# DAC_Channel_12.net
KiCad netlist of a schematic drawn in Altium Designer
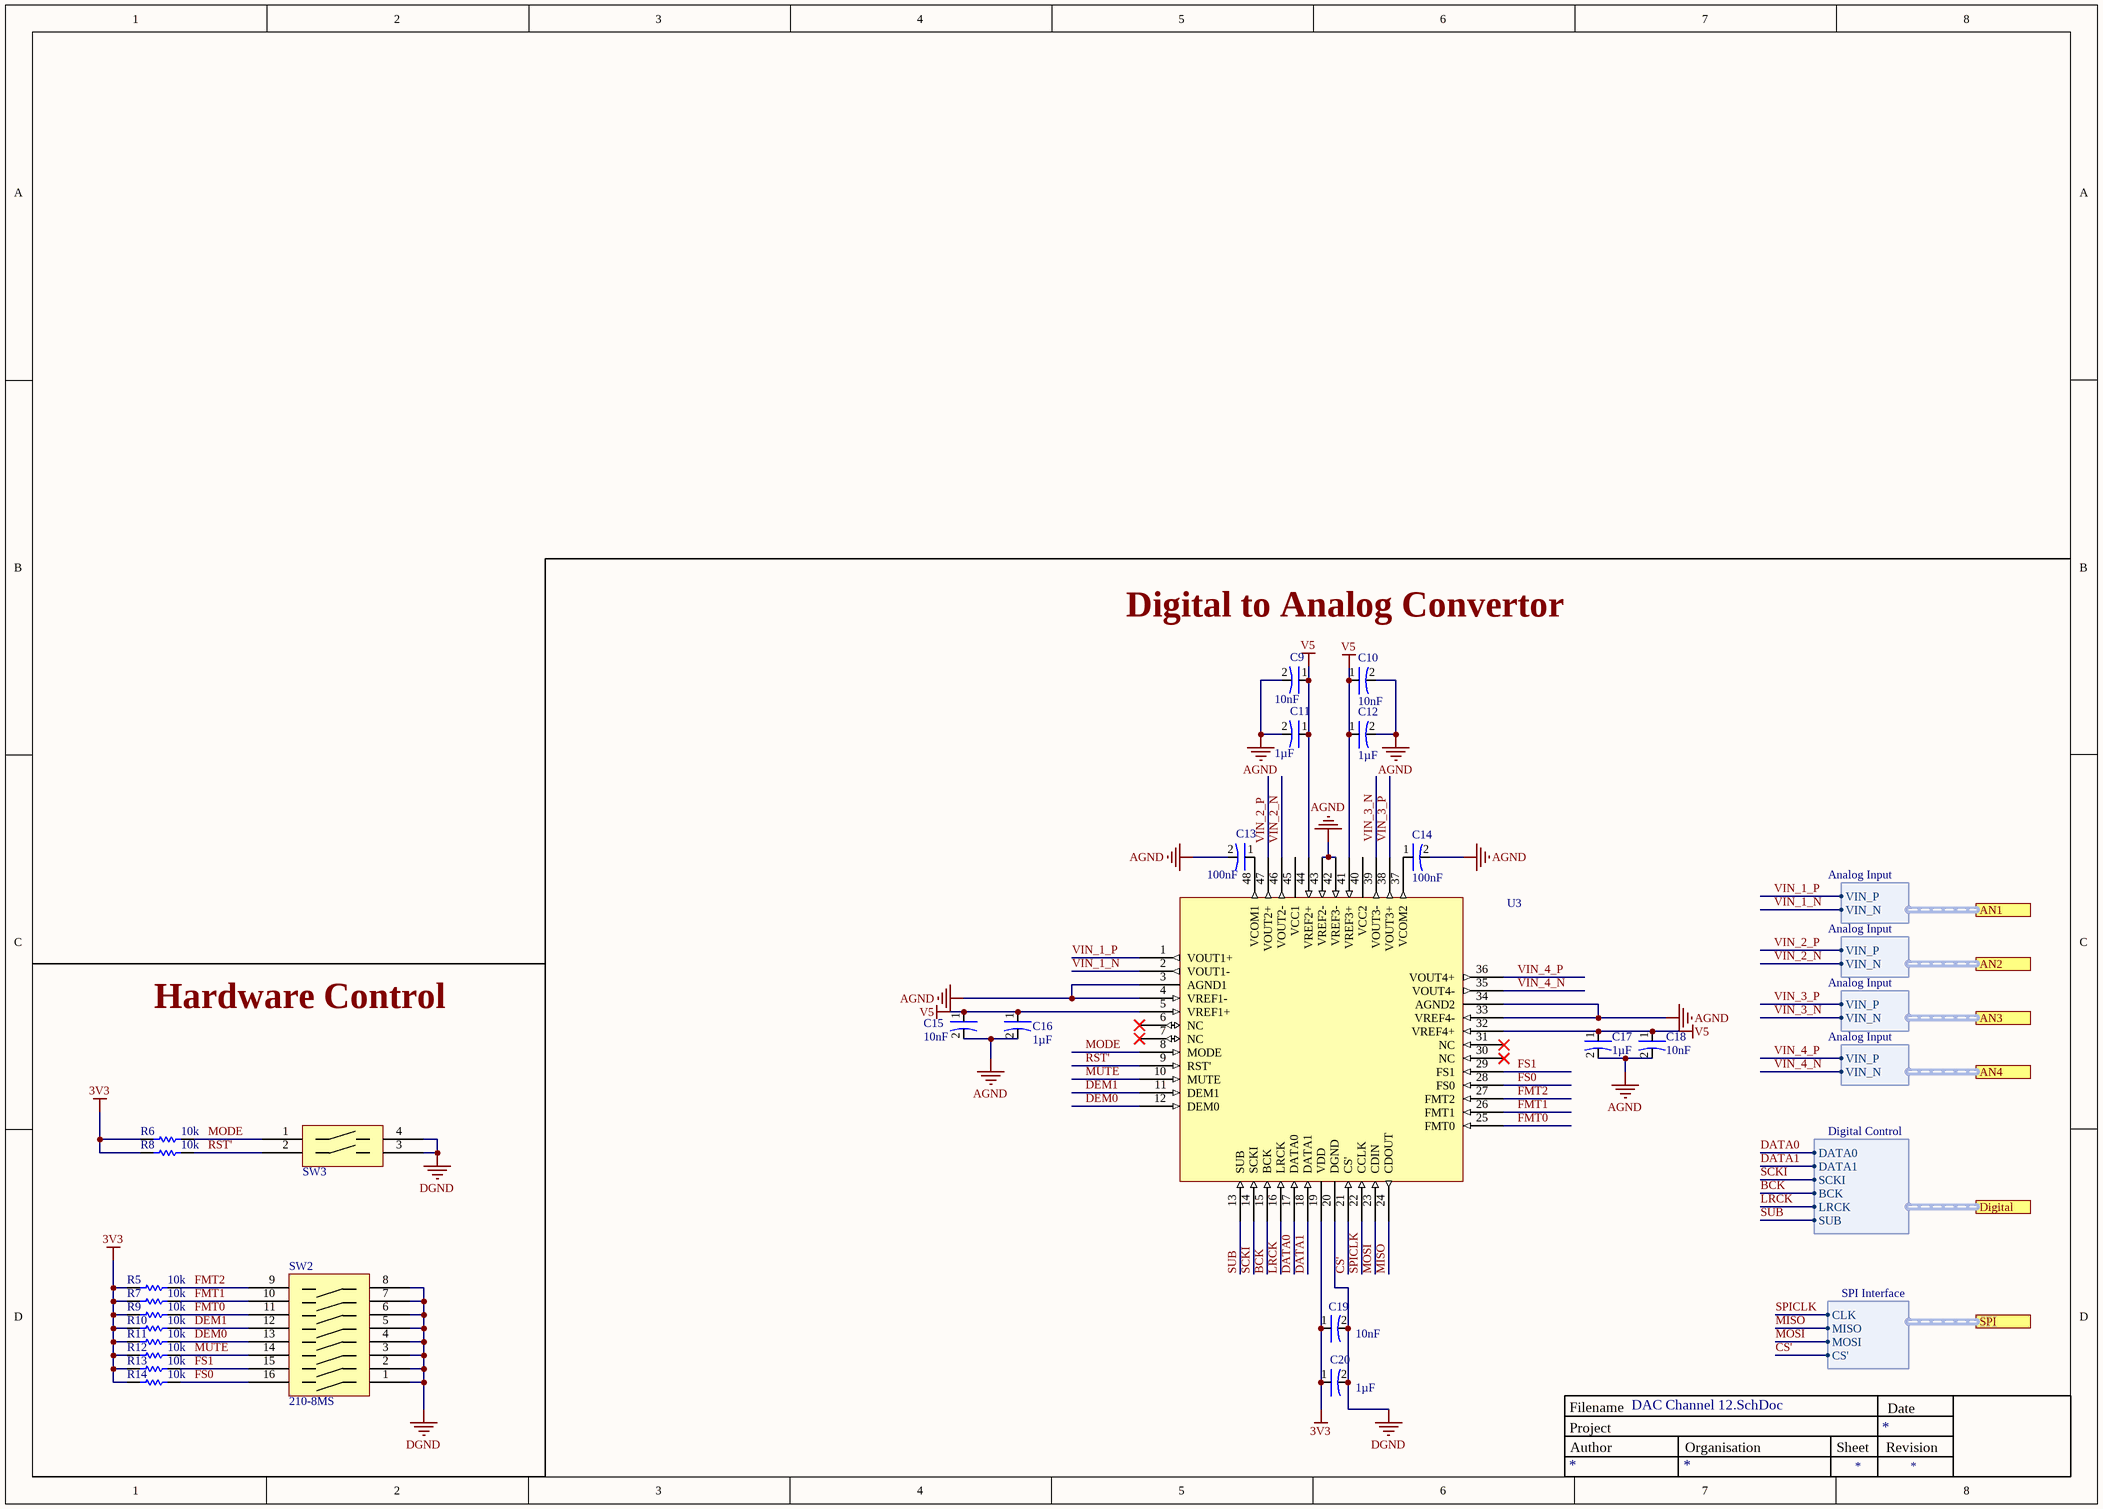
[diagram p0: DAC Channel 12.SchDoc]

(export (version "E")
  (design (tool "Eeschema 10.0.6"))
  (components
    (comp (ref "C9")
      (value "10nF")
      (footprint "0805-M")
      (description "CAP-10nF-CER-0805-50V-X7R-10%")
      (fields
        (field (name "MANUFACTURER") "Generic")
        (field (name "Comment") "CAP 10nF CER 0805 50V X7R 10%")
      )
      (libsource (lib "") (part "Symbol_1"))
    )
    (comp (ref "C10")
      (value "10nF")
      (footprint "0805-M")
      (description "CAP-10nF-CER-0805-50V-X7R-10%")
      (fields
        (field (name "MANUFACTURER") "Generic")
        (field (name "Comment") "CAP 10nF CER 0805 50V X7R 10%")
      )
      (libsource (lib "") (part "Symbol_2"))
    )
    (comp (ref "C11")
      (value "1µF")
      (footprint "0805-L")
      (description "CAP-1uF-CER-0805-50V-X7R-10%")
      (fields (field (name "MANUFACTURER") "Generic") (field (name "Comment") "CAP 1uF CER 0805 50V X7R 10%"))
      (libsource (lib "") (part "Symbol_1"))
    )
    (comp (ref "C12")
      (value "1µF")
      (footprint "0805-L")
      (description "CAP-1uF-CER-0805-50V-X7R-10%")
      (fields (field (name "MANUFACTURER") "Generic") (field (name "Comment") "CAP 1uF CER 0805 50V X7R 10%"))
      (libsource (lib "") (part "Symbol_2"))
    )
    (comp (ref "C13")
      (value "100nF")
      (footprint "0603-M")
      (description "CAP-100nF-CER-0603-50V-X7R-5%")
      (fields
        (field (name "MANUFACTURER") "Generic")
        (field (name "Comment") "CAP 100nF CER 0603 50V X7R 5%")
      )
      (libsource (lib "") (part "Symbol_1"))
    )
    (comp (ref "C14")
      (value "100nF")
      (footprint "0603-M")
      (description "CAP-100nF-CER-0603-50V-X7R-5%")
      (fields
        (field (name "MANUFACTURER") "Generic")
        (field (name "Comment") "CAP 100nF CER 0603 50V X7R 5%")
      )
      (libsource (lib "") (part "Symbol_2"))
    )
    (comp (ref "C15")
      (value "10nF")
      (footprint "0805-M")
      (description "CAP-10nF-CER-0805-50V-X7R-10%")
      (fields
        (field (name "MANUFACTURER") "Generic")
        (field (name "Comment") "CAP 10nF CER 0805 50V X7R 10%")
      )
      (libsource (lib "") (part "Symbol_3"))
    )
    (comp (ref "C16")
      (value "1µF")
      (footprint "0805-L")
      (description "CAP-1uF-CER-0805-50V-X7R-10%")
      (fields (field (name "MANUFACTURER") "Generic") (field (name "Comment") "CAP 1uF CER 0805 50V X7R 10%"))
      (libsource (lib "") (part "Symbol_3"))
    )
    (comp (ref "C17")
      (value "1µF")
      (footprint "0805-L")
      (description "CAP-1uF-CER-0805-50V-X7R-10%")
      (fields (field (name "MANUFACTURER") "Generic") (field (name "Comment") "CAP 1uF CER 0805 50V X7R 10%"))
      (libsource (lib "") (part "Symbol_3"))
    )
    (comp (ref "C18")
      (value "10nF")
      (footprint "0805-M")
      (description "CAP-10nF-CER-0805-50V-X7R-10%")
      (fields
        (field (name "MANUFACTURER") "Generic")
        (field (name "Comment") "CAP 10nF CER 0805 50V X7R 10%")
      )
      (libsource (lib "") (part "Symbol_3"))
    )
    (comp (ref "C19")
      (value "10nF")
      (footprint "0805-M")
      (description "CAP-10nF-CER-0805-50V-X7R-10%")
      (fields
        (field (name "MANUFACTURER") "Generic")
        (field (name "Comment") "CAP 10nF CER 0805 50V X7R 10%")
      )
      (libsource (lib "") (part "Symbol_1"))
    )
    (comp (ref "C20")
      (value "1µF")
      (footprint "0805-L")
      (description "CAP-1uF-CER-0805-50V-X7R-10%")
      (fields (field (name "MANUFACTURER") "Generic") (field (name "Comment") "CAP 1uF CER 0805 50V X7R 10%"))
      (libsource (lib "") (part "Symbol_1"))
    )
    (comp (ref "R5")
      (value "10k")
      (footprint "0805-M")
      (description "RES-10k-0805-125mW-1%")
      (fields (field (name "MANUFACTURER") "Generic") (field (name "Comment") "RES 10k 0805 125mW 1%"))
      (libsource (lib "University of Malta - MEMENTO") (part "Symbol"))
    )
    (comp (ref "R6")
      (value "10k")
      (footprint "0805-M")
      (description "RES-10k-0805-125mW-1%")
      (fields (field (name "MANUFACTURER") "Generic") (field (name "Comment") "RES 10k 0805 125mW 1%"))
      (libsource (lib "University of Malta - MEMENTO") (part "Symbol"))
    )
    (comp (ref "R7")
      (value "10k")
      (footprint "0805-M")
      (description "RES-10k-0805-125mW-1%")
      (fields (field (name "MANUFACTURER") "Generic") (field (name "Comment") "RES 10k 0805 125mW 1%"))
      (libsource (lib "University of Malta - MEMENTO") (part "Symbol"))
    )
    (comp (ref "R8")
      (value "10k")
      (footprint "0805-M")
      (description "RES-10k-0805-125mW-1%")
      (fields (field (name "MANUFACTURER") "Generic") (field (name "Comment") "RES 10k 0805 125mW 1%"))
      (libsource (lib "University of Malta - MEMENTO") (part "Symbol"))
    )
    (comp (ref "R9")
      (value "10k")
      (footprint "0805-M")
      (description "RES-10k-0805-125mW-1%")
      (fields (field (name "MANUFACTURER") "Generic") (field (name "Comment") "RES 10k 0805 125mW 1%"))
      (libsource (lib "University of Malta - MEMENTO") (part "Symbol"))
    )
    (comp (ref "R10")
      (value "10k")
      (footprint "0805-M")
      (description "RES-10k-0805-125mW-1%")
      (fields (field (name "MANUFACTURER") "Generic") (field (name "Comment") "RES 10k 0805 125mW 1%"))
      (libsource (lib "University of Malta - MEMENTO") (part "Symbol"))
    )
    (comp (ref "R11")
      (value "10k")
      (footprint "0805-M")
      (description "RES-10k-0805-125mW-1%")
      (fields (field (name "MANUFACTURER") "Generic") (field (name "Comment") "RES 10k 0805 125mW 1%"))
      (libsource (lib "University of Malta - MEMENTO") (part "Symbol"))
    )
    (comp (ref "R12")
      (value "10k")
      (footprint "0805-M")
      (description "RES-10k-0805-125mW-1%")
      (fields (field (name "MANUFACTURER") "Generic") (field (name "Comment") "RES 10k 0805 125mW 1%"))
      (libsource (lib "University of Malta - MEMENTO") (part "Symbol"))
    )
    (comp (ref "R13")
      (value "10k")
      (footprint "0805-M")
      (description "RES-10k-0805-125mW-1%")
      (fields (field (name "MANUFACTURER") "Generic") (field (name "Comment") "RES 10k 0805 125mW 1%"))
      (libsource (lib "University of Malta - MEMENTO") (part "Symbol"))
    )
    (comp (ref "R14")
      (value "10k")
      (footprint "0805-M")
      (description "RES-10k-0805-125mW-1%")
      (fields (field (name "MANUFACTURER") "Generic") (field (name "Comment") "RES 10k 0805 125mW 1%"))
      (libsource (lib "University of Malta - MEMENTO") (part "Symbol"))
    )
    (comp (ref "SW2")
      (value "210-8MS")
      (footprint "210-8MS")
      (description "SWITCH DIP SMD SPST 8 100mA 50V")
      (fields (field (name "MANUFACTURER") "C&K Components") (field (name "DESIGN ITEM ID") "210-8MS"))
      (libsource (lib "University of Malta - MEMENTO") (part "210-8MS"))
    )
    (comp (ref "SW3")
      (value "210-2MS")
      (footprint "210-2MS-Footprint-1")
      (description "SWITCH DIP SPST 2 100mA 50V")
      (libsource (lib "University of Malta - MEMENTO") (part "210-2MS"))
    )
    (comp (ref "U3")
      (value "PCM4104PFBR")
      (footprint "CQFP50P1170X1170X100-48N")
      (description "Converters - Digital to Analog (DAC) High-End 24-Bit 192kHz, 4-Ch D-S DAC")
      (libsource (lib "University of Malta - MEMENTO") (part "PCM4104PFBR"))
    )
  )
  (nets
    (net (code "7") (name "/BCK") (class "Default")
      (node (ref "U3") (pin "15") (pinfunction "BCK_15") (pintype "input"))
    )
    (net (code "8") (name "/CS'") (class "Default")
      (node (ref "U3") (pin "21") (pinfunction "CS'_21") (pintype "input"))
    )
    (net (code "9") (name "/DATA0") (class "Default")
      (node (ref "U3") (pin "17") (pinfunction "DATA0_17") (pintype "input"))
    )
    (net (code "10") (name "/DATA1") (class "Default")
      (node (ref "U3") (pin "18") (pinfunction "DATA1_18") (pintype "input"))
    )
    (net (code "11") (name "/DEM0") (class "Default")
      (node (ref "R11") (pin "1") (pinfunction "1_1") (pintype "passive"))
      (node (ref "SW2") (pin "13") (pinfunction "SW4.in_13") (pintype "passive"))
      (node (ref "U3") (pin "12") (pinfunction "DEM0_12") (pintype "input"))
    )
    (net (code "12") (name "/DEM1") (class "Default")
      (node (ref "R10") (pin "1") (pinfunction "1_1") (pintype "passive"))
      (node (ref "SW2") (pin "12") (pinfunction "SW1.in_12") (pintype "passive"))
      (node (ref "U3") (pin "11") (pinfunction "DEM1_11") (pintype "input"))
    )
    (net (code "13") (name "/FMT0") (class "Default")
      (node (ref "R9") (pin "1") (pinfunction "1_1") (pintype "passive"))
      (node (ref "SW2") (pin "11") (pinfunction "SW2.in_11") (pintype "passive"))
      (node (ref "U3") (pin "25") (pinfunction "FMT0_25") (pintype "input"))
    )
    (net (code "14") (name "/FMT1") (class "Default")
      (node (ref "R7") (pin "1") (pinfunction "1_1") (pintype "passive"))
      (node (ref "SW2") (pin "10") (pinfunction "SW3.in_10") (pintype "passive"))
      (node (ref "U3") (pin "26") (pinfunction "FMT1_26") (pintype "input"))
    )
    (net (code "15") (name "/FMT2") (class "Default")
      (node (ref "R5") (pin "1") (pinfunction "1_1") (pintype "passive"))
      (node (ref "SW2") (pin "9") (pinfunction "SW4.in_9") (pintype "passive"))
      (node (ref "U3") (pin "27") (pinfunction "FMT2_27") (pintype "input"))
    )
    (net (code "16") (name "/FS0") (class "Default")
      (node (ref "R14") (pin "1") (pinfunction "1_1") (pintype "passive"))
      (node (ref "SW2") (pin "16") (pinfunction "SW1_16") (pintype "passive"))
      (node (ref "U3") (pin "28") (pinfunction "FS0_28") (pintype "input"))
    )
    (net (code "17") (name "/FS1") (class "Default")
      (node (ref "R13") (pin "1") (pinfunction "1_1") (pintype "passive"))
      (node (ref "SW2") (pin "15") (pinfunction "SW2.in_15") (pintype "passive"))
      (node (ref "U3") (pin "29") (pinfunction "FS1_29") (pintype "input"))
    )
    (net (code "18") (name "/LRCK") (class "Default")
      (node (ref "U3") (pin "16") (pinfunction "LRCK_16") (pintype "input"))
    )
    (net (code "19") (name "/MISO") (class "Default")
      (node (ref "U3") (pin "24") (pinfunction "CDOUT_24") (pintype "output"))
    )
    (net (code "20") (name "/MODE") (class "Default")
      (node (ref "R6") (pin "1") (pinfunction "1_1") (pintype "passive"))
      (node (ref "SW3") (pin "1") (pinfunction "1_1") (pintype "passive"))
      (node (ref "U3") (pin "8") (pinfunction "MODE_8") (pintype "input"))
    )
    (net (code "21") (name "/MOSI") (class "Default")
      (node (ref "U3") (pin "23") (pinfunction "CDIN_23") (pintype "input"))
    )
    (net (code "22") (name "/MUTE") (class "Default")
      (node (ref "R12") (pin "1") (pinfunction "1_1") (pintype "passive"))
      (node (ref "SW2") (pin "14") (pinfunction "SW3.in_14") (pintype "passive"))
      (node (ref "U3") (pin "10") (pinfunction "MUTE_10") (pintype "input"))
    )
    (net (code "23") (name "/RST'") (class "Default")
      (node (ref "R8") (pin "1") (pinfunction "1_1") (pintype "passive"))
      (node (ref "SW3") (pin "2") (pinfunction "2_2") (pintype "passive"))
      (node (ref "U3") (pin "9") (pinfunction "RST'_9") (pintype "input"))
    )
    (net (code "24") (name "/SCKI") (class "Default")
      (node (ref "U3") (pin "14") (pinfunction "SCKI_14") (pintype "input"))
    )
    (net (code "25") (name "/SPICLK") (class "Default")
      (node (ref "U3") (pin "22") (pinfunction "CCLK_22") (pintype "input"))
    )
    (net (code "26") (name "/SUB") (class "Default")
      (node (ref "U3") (pin "13") (pinfunction "SUB_13") (pintype "input"))
    )
    (net (code "27") (name "/VIN_1_N") (class "Default")
      (node (ref "U3") (pin "2") (pinfunction "VOUT1-_2") (pintype "output"))
    )
    (net (code "28") (name "/VIN_1_P") (class "Default")
      (node (ref "U3") (pin "1") (pinfunction "VOUT1+_1") (pintype "output"))
    )
    (net (code "29") (name "/VIN_2_N") (class "Default")
      (node (ref "U3") (pin "46") (pinfunction "VOUT2-_46") (pintype "output"))
    )
    (net (code "30") (name "/VIN_2_P") (class "Default")
      (node (ref "U3") (pin "47") (pinfunction "VOUT2+_47") (pintype "output"))
    )
    (net (code "31") (name "/VIN_3_N") (class "Default")
      (node (ref "U3") (pin "39") (pinfunction "VOUT3-_39") (pintype "output"))
    )
    (net (code "32") (name "/VIN_3_P") (class "Default")
      (node (ref "U3") (pin "38") (pinfunction "VOUT3+_38") (pintype "output"))
    )
    (net (code "33") (name "/VIN_4_N") (class "Default")
      (node (ref "U3") (pin "35") (pinfunction "VOUT4-_35") (pintype "output"))
    )
    (net (code "34") (name "/VIN_4_P") (class "Default")
      (node (ref "U3") (pin "36") (pinfunction "VOUT4+_36") (pintype "output"))
    )
    (net (code "38") (name "3V3") (class "Default")
      (node (ref "C19") (pin "1") (pinfunction "Anode_1") (pintype "passive"))
      (node (ref "C20") (pin "1") (pinfunction "Anode_1") (pintype "passive"))
      (node (ref "R10") (pin "2") (pinfunction "2_2") (pintype "passive"))
      (node (ref "R11") (pin "2") (pinfunction "2_2") (pintype "passive"))
      (node (ref "R12") (pin "2") (pinfunction "2_2") (pintype "passive"))
      (node (ref "R13") (pin "2") (pinfunction "2_2") (pintype "passive"))
      (node (ref "R14") (pin "2") (pinfunction "2_2") (pintype "passive"))
      (node (ref "R5") (pin "2") (pinfunction "2_2") (pintype "passive"))
      (node (ref "R6") (pin "2") (pinfunction "2_2") (pintype "passive"))
      (node (ref "R7") (pin "2") (pinfunction "2_2") (pintype "passive"))
      (node (ref "R8") (pin "2") (pinfunction "2_2") (pintype "passive"))
      (node (ref "R9") (pin "2") (pinfunction "2_2") (pintype "passive"))
      (node (ref "U3") (pin "19") (pinfunction "VDD_19") (pintype "power_in"))
    )
    (net (code "39") (name "AGND") (class "Default")
      (node (ref "C10") (pin "2") (pinfunction "Cathode_2") (pintype "passive"))
      (node (ref "C11") (pin "2") (pinfunction "Cathode_2") (pintype "passive"))
      (node (ref "C12") (pin "2") (pinfunction "Cathode_2") (pintype "passive"))
      (node (ref "C13") (pin "2") (pinfunction "Cathode_2") (pintype "passive"))
      (node (ref "C14") (pin "2") (pinfunction "Cathode_2") (pintype "passive"))
      (node (ref "C15") (pin "2") (pinfunction "Cathode_2") (pintype "passive"))
      (node (ref "C16") (pin "2") (pinfunction "Cathode_2") (pintype "passive"))
      (node (ref "C17") (pin "2") (pinfunction "Cathode_2") (pintype "passive"))
      (node (ref "C18") (pin "2") (pinfunction "Cathode_2") (pintype "passive"))
      (node (ref "C9") (pin "2") (pinfunction "Cathode_2") (pintype "passive"))
      (node (ref "U3") (pin "3") (pinfunction "AGND1_3") (pintype "power_in"))
      (node (ref "U3") (pin "33") (pinfunction "VREF4-_33") (pintype "input"))
      (node (ref "U3") (pin "34") (pinfunction "AGND2_34") (pintype "power_in"))
      (node (ref "U3") (pin "4") (pinfunction "VREF1-_4") (pintype "input"))
      (node (ref "U3") (pin "42") (pinfunction "VREF3-_42") (pintype "input"))
      (node (ref "U3") (pin "43") (pinfunction "VREF2-_43") (pintype "input"))
    )
    (net (code "40") (name "DGND") (class "Default")
      (node (ref "C19") (pin "2") (pinfunction "Cathode_2") (pintype "passive"))
      (node (ref "C20") (pin "2") (pinfunction "Cathode_2") (pintype "passive"))
      (node (ref "SW2") (pin "1") (pinfunction "SW1_1") (pintype "passive"))
      (node (ref "SW2") (pin "2") (pinfunction "SW2_2") (pintype "passive"))
      (node (ref "SW2") (pin "3") (pinfunction "SW3_3") (pintype "passive"))
      (node (ref "SW2") (pin "4") (pinfunction "SW4_4") (pintype "passive"))
      (node (ref "SW2") (pin "5") (pinfunction "SW1_5") (pintype "passive"))
      (node (ref "SW2") (pin "6") (pinfunction "SW2_6") (pintype "passive"))
      (node (ref "SW2") (pin "7") (pinfunction "7_7") (pintype "passive"))
      (node (ref "SW2") (pin "8") (pinfunction "SW4_8") (pintype "passive"))
      (node (ref "SW3") (pin "3") (pinfunction "4_3") (pintype "passive"))
      (node (ref "SW3") (pin "4") (pinfunction "4_4") (pintype "passive"))
      (node (ref "U3") (pin "20") (pinfunction "DGND_20") (pintype "power_in"))
    )
    (net (code "41") (name "Net-(C13-Anode)") (class "Default")
      (node (ref "C13") (pin "1") (pinfunction "Anode_1") (pintype "passive"))
      (node (ref "U3") (pin "48") (pinfunction "VCOM1_48") (pintype "output"))
    )
    (net (code "42") (name "Net-(C14-Anode)") (class "Default")
      (node (ref "C14") (pin "1") (pinfunction "Anode_1") (pintype "passive"))
      (node (ref "U3") (pin "37") (pinfunction "VCOM2_37") (pintype "output"))
    )
    (net (code "43") (name "V5") (class "Default")
      (node (ref "C10") (pin "1") (pinfunction "Anode_1") (pintype "passive"))
      (node (ref "C11") (pin "1") (pinfunction "Anode_1") (pintype "passive"))
      (node (ref "C12") (pin "1") (pinfunction "Anode_1") (pintype "passive"))
      (node (ref "C15") (pin "1") (pinfunction "Anode_1") (pintype "passive"))
      (node (ref "C16") (pin "1") (pinfunction "Anode_1") (pintype "passive"))
      (node (ref "C17") (pin "1") (pinfunction "Anode_1") (pintype "passive"))
      (node (ref "C18") (pin "1") (pinfunction "Anode_1") (pintype "passive"))
      (node (ref "C9") (pin "1") (pinfunction "Anode_1") (pintype "passive"))
      (node (ref "U3") (pin "32") (pinfunction "VREF4+_32") (pintype "input"))
      (node (ref "U3") (pin "41") (pinfunction "VREF3+_41") (pintype "input"))
      (node (ref "U3") (pin "44") (pinfunction "VREF2+_44") (pintype "input"))
      (node (ref "U3") (pin "5") (pinfunction "VREF1+_5") (pintype "input"))
    )
    (net (code "44") (name "unconnected-(U3-NC-Pad6)") (class "Default")
      (node (ref "U3") (pin "6") (pinfunction "NC_6") (pintype "bidirectional+no_connect"))
    )
    (net (code "45") (name "unconnected-(U3-NC-Pad7)") (class "Default")
      (node (ref "U3") (pin "7") (pinfunction "NC_7") (pintype "bidirectional+no_connect"))
    )
    (net (code "46") (name "unconnected-(U3-NC-Pad30)") (class "Default")
      (node (ref "U3") (pin "30") (pinfunction "NC_30") (pintype "input+no_connect"))
    )
    (net (code "47") (name "unconnected-(U3-NC-Pad31)") (class "Default")
      (node (ref "U3") (pin "31") (pinfunction "NC_31") (pintype "input+no_connect"))
    )
    (net (code "48") (name "unconnected-(U3-VCC1-Pad45)") (class "Default")
      (node (ref "U3") (pin "45") (pinfunction "VCC1_45") (pintype "power_in"))
    )
    (net (code "49") (name "unconnected-(U3-VCC2-Pad40)") (class "Default")
      (node (ref "U3") (pin "40") (pinfunction "VCC2_40") (pintype "power_in"))
    )
  )
)
